# PCB-BI8-3x5C3.net
KiCad netlist of a schematic drawn in EAGLE
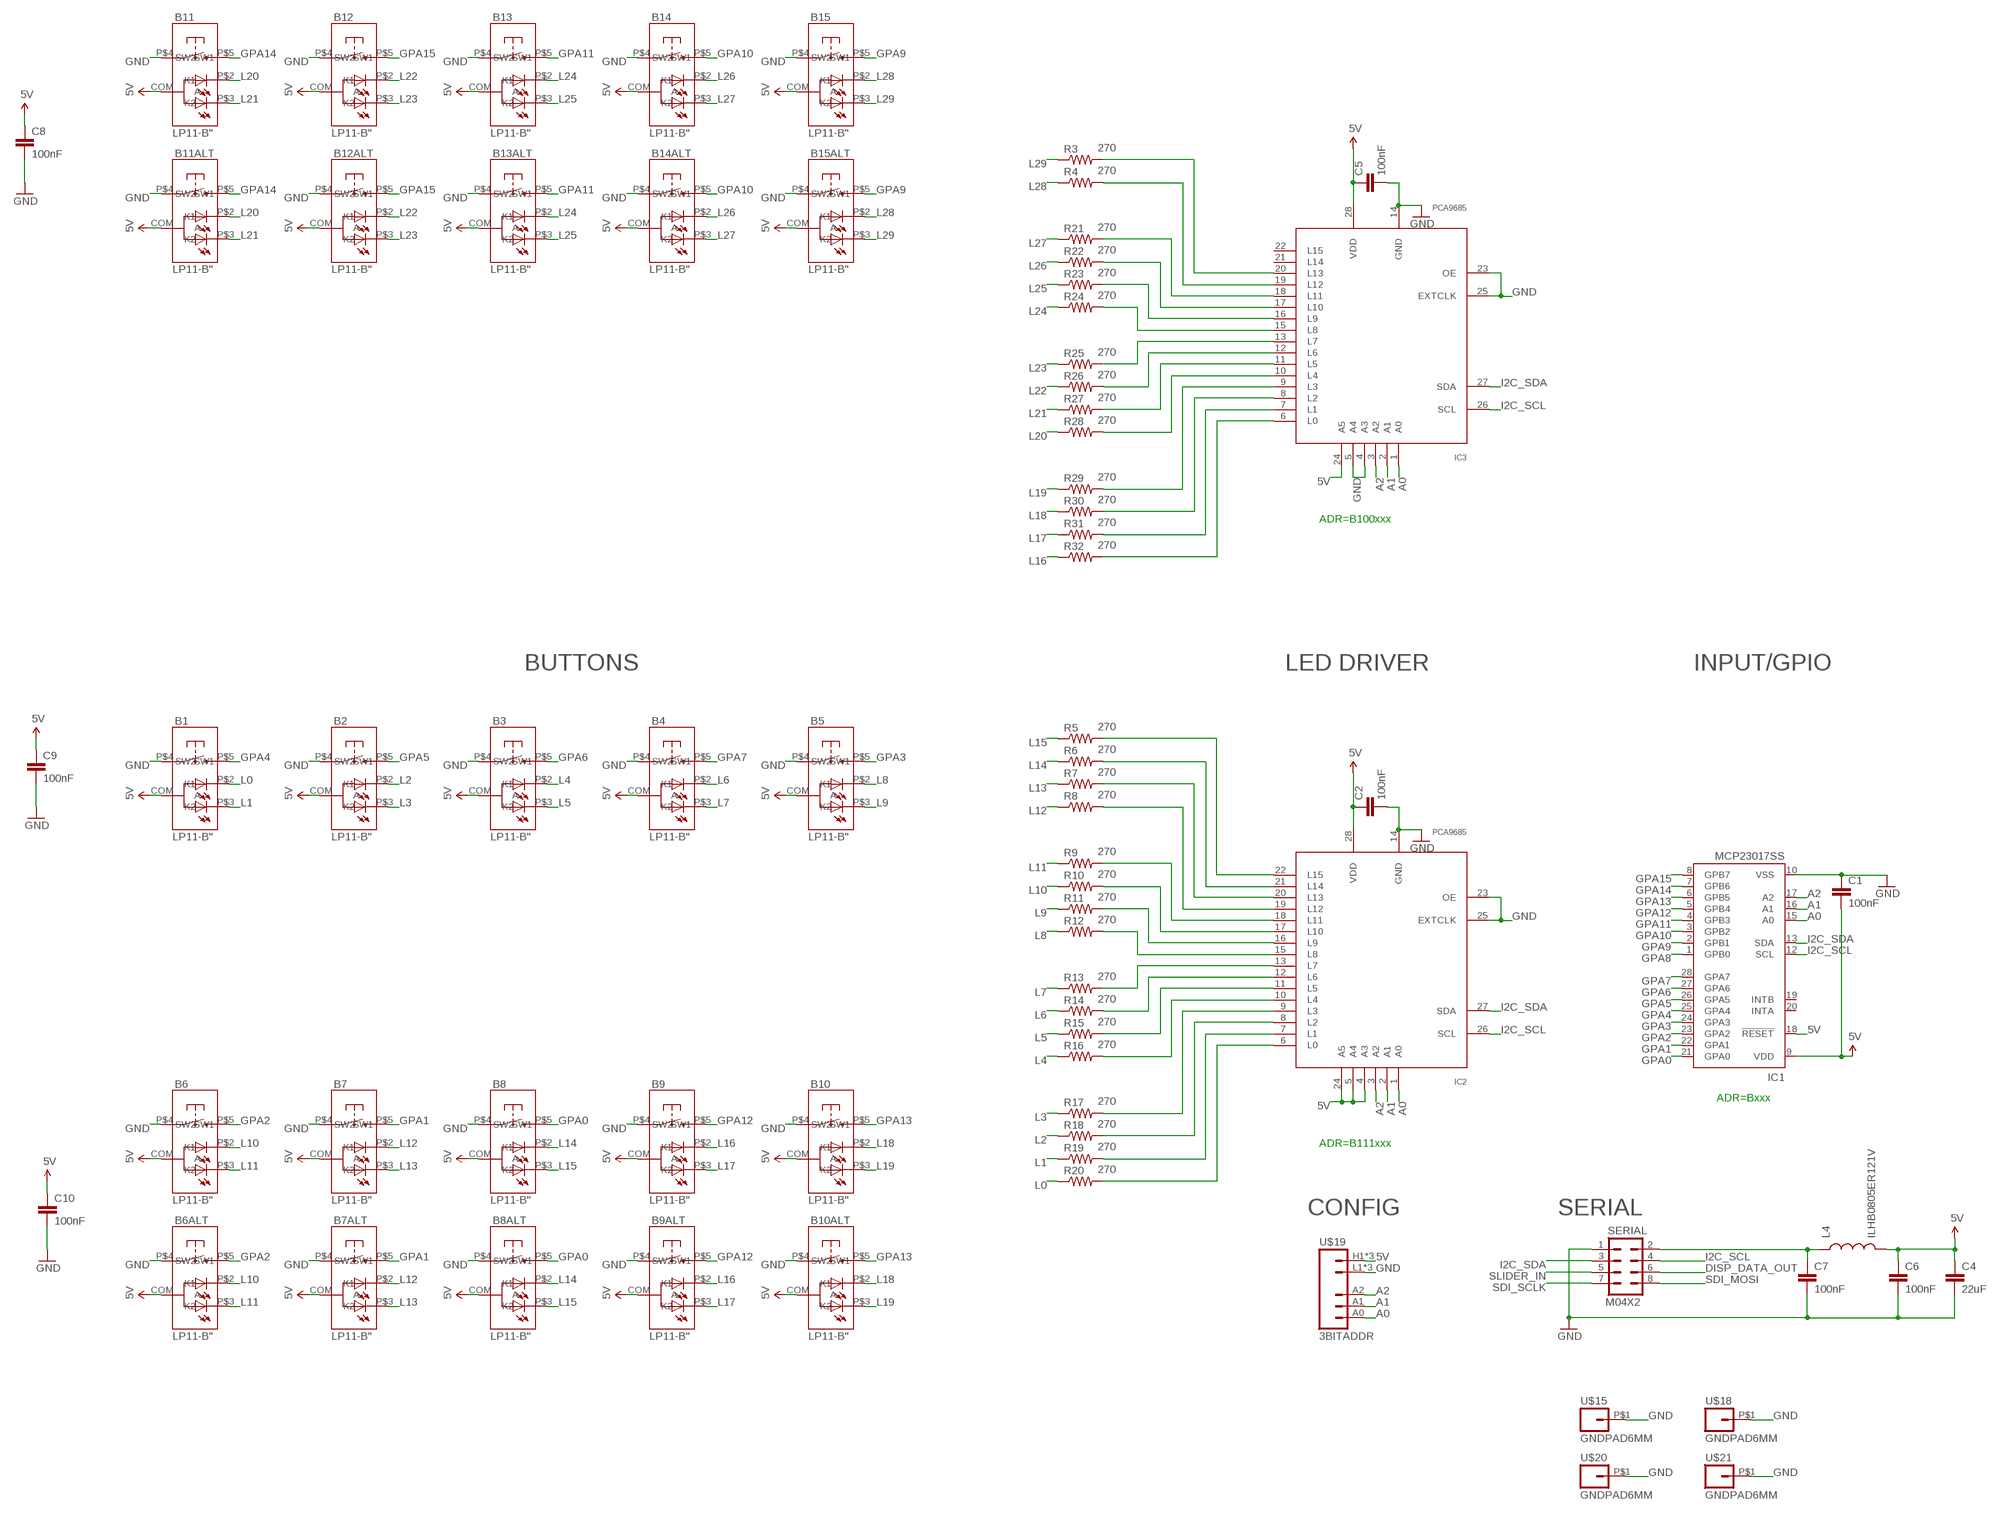
[diagram p0: schematic, sheet 1]

(export (version "E")
  (design (tool "Eeschema 10.0.6"))
  (components
    (comp (ref "B1")
      (value "LP11-B\"")
      (footprint "eagle-import:LP11")
      (libsource (lib "eagle-import") (part "LP11-B{dblquote}"))
    )
    (comp (ref "B2")
      (value "LP11-B\"")
      (footprint "eagle-import:LP11")
      (libsource (lib "eagle-import") (part "LP11-B{dblquote}"))
    )
    (comp (ref "B3")
      (value "LP11-B\"")
      (footprint "eagle-import:LP11")
      (libsource (lib "eagle-import") (part "LP11-B{dblquote}"))
    )
    (comp (ref "B4")
      (value "LP11-B\"")
      (footprint "eagle-import:LP11")
      (libsource (lib "eagle-import") (part "LP11-B{dblquote}"))
    )
    (comp (ref "B5")
      (value "LP11-B\"")
      (footprint "eagle-import:LP11")
      (libsource (lib "eagle-import") (part "LP11-B{dblquote}"))
    )
    (comp (ref "B6")
      (value "LP11-B\"")
      (footprint "eagle-import:LP11")
      (libsource (lib "eagle-import") (part "LP11-B{dblquote}"))
    )
    (comp (ref "B6ALT")
      (value "LP11-B\"")
      (footprint "eagle-import:LP11")
      (libsource (lib "eagle-import") (part "LP11-B{dblquote}"))
    )
    (comp (ref "B7")
      (value "LP11-B\"")
      (footprint "eagle-import:LP11")
      (libsource (lib "eagle-import") (part "LP11-B{dblquote}"))
    )
    (comp (ref "B7ALT")
      (value "LP11-B\"")
      (footprint "eagle-import:LP11")
      (libsource (lib "eagle-import") (part "LP11-B{dblquote}"))
    )
    (comp (ref "B8")
      (value "LP11-B\"")
      (footprint "eagle-import:LP11")
      (libsource (lib "eagle-import") (part "LP11-B{dblquote}"))
    )
    (comp (ref "B8ALT")
      (value "LP11-B\"")
      (footprint "eagle-import:LP11")
      (libsource (lib "eagle-import") (part "LP11-B{dblquote}"))
    )
    (comp (ref "B9")
      (value "LP11-B\"")
      (footprint "eagle-import:LP11")
      (libsource (lib "eagle-import") (part "LP11-B{dblquote}"))
    )
    (comp (ref "B9ALT")
      (value "LP11-B\"")
      (footprint "eagle-import:LP11")
      (libsource (lib "eagle-import") (part "LP11-B{dblquote}"))
    )
    (comp (ref "B10")
      (value "LP11-B\"")
      (footprint "eagle-import:LP11")
      (libsource (lib "eagle-import") (part "LP11-B{dblquote}"))
    )
    (comp (ref "B10ALT")
      (value "LP11-B\"")
      (footprint "eagle-import:LP11")
      (libsource (lib "eagle-import") (part "LP11-B{dblquote}"))
    )
    (comp (ref "B11")
      (value "LP11-B\"")
      (footprint "eagle-import:LP11")
      (libsource (lib "eagle-import") (part "LP11-B{dblquote}"))
    )
    (comp (ref "B11ALT")
      (value "LP11-B\"")
      (footprint "eagle-import:LP11")
      (libsource (lib "eagle-import") (part "LP11-B{dblquote}"))
    )
    (comp (ref "B12")
      (value "LP11-B\"")
      (footprint "eagle-import:LP11")
      (libsource (lib "eagle-import") (part "LP11-B{dblquote}"))
    )
    (comp (ref "B12ALT")
      (value "LP11-B\"")
      (footprint "eagle-import:LP11")
      (libsource (lib "eagle-import") (part "LP11-B{dblquote}"))
    )
    (comp (ref "B13")
      (value "LP11-B\"")
      (footprint "eagle-import:LP11")
      (libsource (lib "eagle-import") (part "LP11-B{dblquote}"))
    )
    (comp (ref "B13ALT")
      (value "LP11-B\"")
      (footprint "eagle-import:LP11")
      (libsource (lib "eagle-import") (part "LP11-B{dblquote}"))
    )
    (comp (ref "B14")
      (value "LP11-B\"")
      (footprint "eagle-import:LP11")
      (libsource (lib "eagle-import") (part "LP11-B{dblquote}"))
    )
    (comp (ref "B14ALT")
      (value "LP11-B\"")
      (footprint "eagle-import:LP11")
      (libsource (lib "eagle-import") (part "LP11-B{dblquote}"))
    )
    (comp (ref "B15")
      (value "LP11-B\"")
      (footprint "eagle-import:LP11")
      (libsource (lib "eagle-import") (part "LP11-B{dblquote}"))
    )
    (comp (ref "B15ALT")
      (value "LP11-B\"")
      (footprint "eagle-import:LP11")
      (libsource (lib "eagle-import") (part "LP11-B{dblquote}"))
    )
    (comp (ref "C1")
      (value "100nF")
      (footprint "eagle-import:0603-CAP")
      (libsource (lib "eagle-import") (part "CAP0603-CAP"))
    )
    (comp (ref "C2")
      (value "100nF")
      (footprint "eagle-import:0603-CAP")
      (libsource (lib "eagle-import") (part "CAP0603-CAP"))
    )
    (comp (ref "C4")
      (value "22uF")
      (footprint "eagle-import:0805")
      (libsource (lib "eagle-import") (part "CAP0805"))
    )
    (comp (ref "C5")
      (value "100nF")
      (footprint "eagle-import:0603-CAP")
      (libsource (lib "eagle-import") (part "CAP0603-CAP"))
    )
    (comp (ref "C6")
      (value "100nF")
      (footprint "eagle-import:0603-CAP")
      (libsource (lib "eagle-import") (part "CAP0603-CAP"))
    )
    (comp (ref "C7")
      (value "100nF")
      (footprint "eagle-import:0603-CAP")
      (libsource (lib "eagle-import") (part "CAP0603-CAP"))
    )
    (comp (ref "C8")
      (value "100nF")
      (footprint "eagle-import:0603-CAP")
      (libsource (lib "eagle-import") (part "CAP0603-CAP"))
    )
    (comp (ref "C9")
      (value "100nF")
      (footprint "eagle-import:0603-CAP")
      (libsource (lib "eagle-import") (part "CAP0603-CAP"))
    )
    (comp (ref "C10")
      (value "100nF")
      (footprint "eagle-import:0603-CAP")
      (libsource (lib "eagle-import") (part "CAP0603-CAP"))
    )
    (comp (ref "IC1")
      (value "MCP23017SS")
      (footprint "eagle-import:SSOP28")
      (fields
        (field (name "MF") "MICROCHIP")
        (field (name "MPN") "MCP23017-E/SS")
        (field (name "MPN_1") "MCP23017-E/SS")
        (field (name "OC_FARNELL") "1467674")
        (field (name "OC_NEWARK") "31K2960")
      )
      (libsource (lib "eagle-import") (part "MCP23017SS"))
    )
    (comp (ref "IC2")
      (value "PCA9685")
      (footprint "eagle-import:TSSOP28")
      (libsource (lib "eagle-import") (part "PCA9685"))
    )
    (comp (ref "IC3")
      (value "PCA9685")
      (footprint "eagle-import:TSSOP28")
      (libsource (lib "eagle-import") (part "PCA9685"))
    )
    (comp (ref "L4")
      (value "ILHB0805ER121V")
      (footprint "eagle-import:0805")
      (libsource (lib "eagle-import") (part "INDUCTOR0805"))
    )
    (comp (ref "R3")
      (value "270")
      (footprint "eagle-import:0603-RES")
      (libsource (lib "eagle-import") (part "RESISTOR0603-RES"))
    )
    (comp (ref "R4")
      (value "270")
      (footprint "eagle-import:0603-RES")
      (libsource (lib "eagle-import") (part "RESISTOR0603-RES"))
    )
    (comp (ref "R5")
      (value "270")
      (footprint "eagle-import:0603-RES")
      (libsource (lib "eagle-import") (part "RESISTOR0603-RES"))
    )
    (comp (ref "R6")
      (value "270")
      (footprint "eagle-import:0603-RES")
      (libsource (lib "eagle-import") (part "RESISTOR0603-RES"))
    )
    (comp (ref "R7")
      (value "270")
      (footprint "eagle-import:0603-RES")
      (libsource (lib "eagle-import") (part "RESISTOR0603-RES"))
    )
    (comp (ref "R8")
      (value "270")
      (footprint "eagle-import:0603-RES")
      (libsource (lib "eagle-import") (part "RESISTOR0603-RES"))
    )
    (comp (ref "R9")
      (value "270")
      (footprint "eagle-import:0603-RES")
      (libsource (lib "eagle-import") (part "RESISTOR0603-RES"))
    )
    (comp (ref "R10")
      (value "270")
      (footprint "eagle-import:0603-RES")
      (libsource (lib "eagle-import") (part "RESISTOR0603-RES"))
    )
    (comp (ref "R11")
      (value "270")
      (footprint "eagle-import:0603-RES")
      (libsource (lib "eagle-import") (part "RESISTOR0603-RES"))
    )
    (comp (ref "R12")
      (value "270")
      (footprint "eagle-import:0603-RES")
      (libsource (lib "eagle-import") (part "RESISTOR0603-RES"))
    )
    (comp (ref "R13")
      (value "270")
      (footprint "eagle-import:0603-RES")
      (libsource (lib "eagle-import") (part "RESISTOR0603-RES"))
    )
    (comp (ref "R14")
      (value "270")
      (footprint "eagle-import:0603-RES")
      (libsource (lib "eagle-import") (part "RESISTOR0603-RES"))
    )
    (comp (ref "R15")
      (value "270")
      (footprint "eagle-import:0603-RES")
      (libsource (lib "eagle-import") (part "RESISTOR0603-RES"))
    )
    (comp (ref "R16")
      (value "270")
      (footprint "eagle-import:0603-RES")
      (libsource (lib "eagle-import") (part "RESISTOR0603-RES"))
    )
    (comp (ref "R17")
      (value "270")
      (footprint "eagle-import:0603-RES")
      (libsource (lib "eagle-import") (part "RESISTOR0603-RES"))
    )
    (comp (ref "R18")
      (value "270")
      (footprint "eagle-import:0603-RES")
      (libsource (lib "eagle-import") (part "RESISTOR0603-RES"))
    )
    (comp (ref "R19")
      (value "270")
      (footprint "eagle-import:0603-RES")
      (libsource (lib "eagle-import") (part "RESISTOR0603-RES"))
    )
    (comp (ref "R20")
      (value "270")
      (footprint "eagle-import:0603-RES")
      (libsource (lib "eagle-import") (part "RESISTOR0603-RES"))
    )
    (comp (ref "R21")
      (value "270")
      (footprint "eagle-import:0603-RES")
      (libsource (lib "eagle-import") (part "RESISTOR0603-RES"))
    )
    (comp (ref "R22")
      (value "270")
      (footprint "eagle-import:0603-RES")
      (libsource (lib "eagle-import") (part "RESISTOR0603-RES"))
    )
    (comp (ref "R23")
      (value "270")
      (footprint "eagle-import:0603-RES")
      (libsource (lib "eagle-import") (part "RESISTOR0603-RES"))
    )
    (comp (ref "R24")
      (value "270")
      (footprint "eagle-import:0603-RES")
      (libsource (lib "eagle-import") (part "RESISTOR0603-RES"))
    )
    (comp (ref "R25")
      (value "270")
      (footprint "eagle-import:0603-RES")
      (libsource (lib "eagle-import") (part "RESISTOR0603-RES"))
    )
    (comp (ref "R26")
      (value "270")
      (footprint "eagle-import:0603-RES")
      (libsource (lib "eagle-import") (part "RESISTOR0603-RES"))
    )
    (comp (ref "R27")
      (value "270")
      (footprint "eagle-import:0603-RES")
      (libsource (lib "eagle-import") (part "RESISTOR0603-RES"))
    )
    (comp (ref "R28")
      (value "270")
      (footprint "eagle-import:0603-RES")
      (libsource (lib "eagle-import") (part "RESISTOR0603-RES"))
    )
    (comp (ref "R29")
      (value "270")
      (footprint "eagle-import:0603-RES")
      (libsource (lib "eagle-import") (part "RESISTOR0603-RES"))
    )
    (comp (ref "R30")
      (value "270")
      (footprint "eagle-import:0603-RES")
      (libsource (lib "eagle-import") (part "RESISTOR0603-RES"))
    )
    (comp (ref "R31")
      (value "270")
      (footprint "eagle-import:0603-RES")
      (libsource (lib "eagle-import") (part "RESISTOR0603-RES"))
    )
    (comp (ref "R32")
      (value "270")
      (footprint "eagle-import:0603-RES")
      (libsource (lib "eagle-import") (part "RESISTOR0603-RES"))
    )
    (comp (ref "SERIAL")
      (value "M04X2")
      (footprint "eagle-import:2X4")
      (libsource (lib "eagle-import") (part "M04X2"))
    )
    (comp (ref "U$15")
      (value "GNDPAD6MM")
      (footprint "eagle-import:3.2MMPAD6MM")
      (libsource (lib "eagle-import") (part "GNDPAD6MM"))
    )
    (comp (ref "U$18")
      (value "GNDPAD6MM")
      (footprint "eagle-import:3.2MMPAD6MM")
      (libsource (lib "eagle-import") (part "GNDPAD6MM"))
    )
    (comp (ref "U$19")
      (value "3BITADDR")
      (footprint "eagle-import:3BITADDR")
      (libsource (lib "eagle-import") (part "3BITADDR"))
    )
    (comp (ref "U$20")
      (value "GNDPAD6MM")
      (footprint "eagle-import:3.2MMPAD6MM")
      (libsource (lib "eagle-import") (part "GNDPAD6MM"))
    )
    (comp (ref "U$21")
      (value "GNDPAD6MM")
      (footprint "eagle-import:3.2MMPAD6MM")
      (libsource (lib "eagle-import") (part "GNDPAD6MM"))
    )
  )
  (nets
    (net (code "1") (name "5V") (class "Default")
      (node (ref "B1") (pin "COM") (pinfunction "A_COM") (pintype "bidirectional"))
      (node (ref "B10") (pin "COM") (pinfunction "A_COM") (pintype "bidirectional"))
      (node (ref "B10ALT") (pin "COM") (pinfunction "A_COM") (pintype "bidirectional"))
      (node (ref "B11") (pin "COM") (pinfunction "A_COM") (pintype "bidirectional"))
      (node (ref "B11ALT") (pin "COM") (pinfunction "A_COM") (pintype "bidirectional"))
      (node (ref "B12") (pin "COM") (pinfunction "A_COM") (pintype "bidirectional"))
      (node (ref "B12ALT") (pin "COM") (pinfunction "A_COM") (pintype "bidirectional"))
      (node (ref "B13") (pin "COM") (pinfunction "A_COM") (pintype "bidirectional"))
      (node (ref "B13ALT") (pin "COM") (pinfunction "A_COM") (pintype "bidirectional"))
      (node (ref "B14") (pin "COM") (pinfunction "A_COM") (pintype "bidirectional"))
      (node (ref "B14ALT") (pin "COM") (pinfunction "A_COM") (pintype "bidirectional"))
      (node (ref "B15") (pin "COM") (pinfunction "A_COM") (pintype "bidirectional"))
      (node (ref "B15ALT") (pin "COM") (pinfunction "A_COM") (pintype "bidirectional"))
      (node (ref "B2") (pin "COM") (pinfunction "A_COM") (pintype "bidirectional"))
      (node (ref "B3") (pin "COM") (pinfunction "A_COM") (pintype "bidirectional"))
      (node (ref "B4") (pin "COM") (pinfunction "A_COM") (pintype "bidirectional"))
      (node (ref "B5") (pin "COM") (pinfunction "A_COM") (pintype "bidirectional"))
      (node (ref "B6") (pin "COM") (pinfunction "A_COM") (pintype "bidirectional"))
      (node (ref "B6ALT") (pin "COM") (pinfunction "A_COM") (pintype "bidirectional"))
      (node (ref "B7") (pin "COM") (pinfunction "A_COM") (pintype "bidirectional"))
      (node (ref "B7ALT") (pin "COM") (pinfunction "A_COM") (pintype "bidirectional"))
      (node (ref "B8") (pin "COM") (pinfunction "A_COM") (pintype "bidirectional"))
      (node (ref "B8ALT") (pin "COM") (pinfunction "A_COM") (pintype "bidirectional"))
      (node (ref "B9") (pin "COM") (pinfunction "A_COM") (pintype "bidirectional"))
      (node (ref "B9ALT") (pin "COM") (pinfunction "A_COM") (pintype "bidirectional"))
      (node (ref "C1") (pin "2") (pinfunction "2_2") (pintype "passive"))
      (node (ref "C10") (pin "1") (pinfunction "1_1") (pintype "passive"))
      (node (ref "C2") (pin "1") (pinfunction "1_1") (pintype "passive"))
      (node (ref "C4") (pin "1") (pinfunction "1_1") (pintype "passive"))
      (node (ref "C5") (pin "1") (pinfunction "1_1") (pintype "passive"))
      (node (ref "C6") (pin "1") (pinfunction "1_1") (pintype "passive"))
      (node (ref "C8") (pin "1") (pinfunction "1_1") (pintype "passive"))
      (node (ref "C9") (pin "1") (pinfunction "1_1") (pintype "passive"))
      (node (ref "IC1") (pin "18") (pinfunction "~{RESET}_18") (pintype "input"))
      (node (ref "IC1") (pin "9") (pinfunction "VDD_9") (pintype "power_in"))
      (node (ref "IC2") (pin "24") (pinfunction "A5_24") (pintype "input"))
      (node (ref "IC2") (pin "28") (pinfunction "VDD_28") (pintype "power_in"))
      (node (ref "IC2") (pin "4") (pinfunction "A3_4") (pintype "input"))
      (node (ref "IC2") (pin "5") (pinfunction "A4_5") (pintype "input"))
      (node (ref "IC3") (pin "24") (pinfunction "A5_24") (pintype "input"))
      (node (ref "IC3") (pin "28") (pinfunction "VDD_28") (pintype "power_in"))
      (node (ref "L4") (pin "2") (pinfunction "2_2") (pintype "passive"))
      (node (ref "U$19") (pin "H1") (pinfunction "VCC_H1") (pintype "passive"))
      (node (ref "U$19") (pin "H2") (pinfunction "VCC_H2") (pintype "passive"))
      (node (ref "U$19") (pin "H3") (pinfunction "VCC_H3") (pintype "passive"))
    )
    (net (code "2") (name "A0") (class "Default")
      (node (ref "IC1") (pin "15") (pinfunction "A0_15") (pintype "input"))
      (node (ref "IC2") (pin "1") (pinfunction "A0_1") (pintype "input"))
      (node (ref "IC3") (pin "1") (pinfunction "A0_1") (pintype "input"))
      (node (ref "U$19") (pin "A0") (pinfunction "A0_A0") (pintype "passive"))
    )
    (net (code "3") (name "A1") (class "Default")
      (node (ref "IC1") (pin "16") (pinfunction "A1_16") (pintype "input"))
      (node (ref "IC2") (pin "2") (pinfunction "A1_2") (pintype "input"))
      (node (ref "IC3") (pin "2") (pinfunction "A1_2") (pintype "input"))
      (node (ref "U$19") (pin "A1") (pinfunction "A1_A1") (pintype "passive"))
    )
    (net (code "4") (name "A2") (class "Default")
      (node (ref "IC1") (pin "17") (pinfunction "A2_17") (pintype "input"))
      (node (ref "IC2") (pin "3") (pinfunction "A2_3") (pintype "input"))
      (node (ref "IC3") (pin "3") (pinfunction "A2_3") (pintype "input"))
      (node (ref "U$19") (pin "A2") (pinfunction "A2_A2") (pintype "passive"))
    )
    (net (code "5") (name "DISP_DATA_OUT") (class "Default")
      (node (ref "SERIAL") (pin "6") (pinfunction "6_6") (pintype "passive"))
    )
    (net (code "6") (name "GND") (class "Default")
      (node (ref "B1") (pin "P$4") (pinfunction "SW1_P$4") (pintype "bidirectional"))
      (node (ref "B10") (pin "P$4") (pinfunction "SW1_P$4") (pintype "bidirectional"))
      (node (ref "B10ALT") (pin "P$4") (pinfunction "SW1_P$4") (pintype "bidirectional"))
      (node (ref "B11") (pin "P$4") (pinfunction "SW1_P$4") (pintype "bidirectional"))
      (node (ref "B11ALT") (pin "P$4") (pinfunction "SW1_P$4") (pintype "bidirectional"))
      (node (ref "B12") (pin "P$4") (pinfunction "SW1_P$4") (pintype "bidirectional"))
      (node (ref "B12ALT") (pin "P$4") (pinfunction "SW1_P$4") (pintype "bidirectional"))
      (node (ref "B13") (pin "P$4") (pinfunction "SW1_P$4") (pintype "bidirectional"))
      (node (ref "B13ALT") (pin "P$4") (pinfunction "SW1_P$4") (pintype "bidirectional"))
      (node (ref "B14") (pin "P$4") (pinfunction "SW1_P$4") (pintype "bidirectional"))
      (node (ref "B14ALT") (pin "P$4") (pinfunction "SW1_P$4") (pintype "bidirectional"))
      (node (ref "B15") (pin "P$4") (pinfunction "SW1_P$4") (pintype "bidirectional"))
      (node (ref "B15ALT") (pin "P$4") (pinfunction "SW1_P$4") (pintype "bidirectional"))
      (node (ref "B2") (pin "P$4") (pinfunction "SW1_P$4") (pintype "bidirectional"))
      (node (ref "B3") (pin "P$4") (pinfunction "SW1_P$4") (pintype "bidirectional"))
      (node (ref "B4") (pin "P$4") (pinfunction "SW1_P$4") (pintype "bidirectional"))
      (node (ref "B5") (pin "P$4") (pinfunction "SW1_P$4") (pintype "bidirectional"))
      (node (ref "B6") (pin "P$4") (pinfunction "SW1_P$4") (pintype "bidirectional"))
      (node (ref "B6ALT") (pin "P$4") (pinfunction "SW1_P$4") (pintype "bidirectional"))
      (node (ref "B7") (pin "P$4") (pinfunction "SW1_P$4") (pintype "bidirectional"))
      (node (ref "B7ALT") (pin "P$4") (pinfunction "SW1_P$4") (pintype "bidirectional"))
      (node (ref "B8") (pin "P$4") (pinfunction "SW1_P$4") (pintype "bidirectional"))
      (node (ref "B8ALT") (pin "P$4") (pinfunction "SW1_P$4") (pintype "bidirectional"))
      (node (ref "B9") (pin "P$4") (pinfunction "SW1_P$4") (pintype "bidirectional"))
      (node (ref "B9ALT") (pin "P$4") (pinfunction "SW1_P$4") (pintype "bidirectional"))
      (node (ref "C1") (pin "1") (pinfunction "1_1") (pintype "passive"))
      (node (ref "C10") (pin "2") (pinfunction "2_2") (pintype "passive"))
      (node (ref "C2") (pin "2") (pinfunction "2_2") (pintype "passive"))
      (node (ref "C4") (pin "2") (pinfunction "2_2") (pintype "passive"))
      (node (ref "C5") (pin "2") (pinfunction "2_2") (pintype "passive"))
      (node (ref "C6") (pin "2") (pinfunction "2_2") (pintype "passive"))
      (node (ref "C7") (pin "2") (pinfunction "2_2") (pintype "passive"))
      (node (ref "C8") (pin "2") (pinfunction "2_2") (pintype "passive"))
      (node (ref "C9") (pin "2") (pinfunction "2_2") (pintype "passive"))
      (node (ref "IC1") (pin "10") (pinfunction "VSS_10") (pintype "power_in"))
      (node (ref "IC2") (pin "14") (pinfunction "GND_14") (pintype "power_in"))
      (node (ref "IC2") (pin "23") (pinfunction "OE_23") (pintype "input"))
      (node (ref "IC2") (pin "25") (pinfunction "EXTCLK_25") (pintype "input"))
      (node (ref "IC3") (pin "14") (pinfunction "GND_14") (pintype "power_in"))
      (node (ref "IC3") (pin "23") (pinfunction "OE_23") (pintype "input"))
      (node (ref "IC3") (pin "25") (pinfunction "EXTCLK_25") (pintype "input"))
      (node (ref "IC3") (pin "4") (pinfunction "A3_4") (pintype "input"))
      (node (ref "IC3") (pin "5") (pinfunction "A4_5") (pintype "input"))
      (node (ref "SERIAL") (pin "1") (pinfunction "1_1") (pintype "passive"))
      (node (ref "U$15") (pin "P$1") (pinfunction "1_P$1") (pintype "passive"))
      (node (ref "U$18") (pin "P$1") (pinfunction "1_P$1") (pintype "passive"))
      (node (ref "U$19") (pin "L1") (pinfunction "GND_L1") (pintype "passive"))
      (node (ref "U$19") (pin "L2") (pinfunction "GND_L2") (pintype "passive"))
      (node (ref "U$19") (pin "L3") (pinfunction "GND_L3") (pintype "passive"))
      (node (ref "U$20") (pin "P$1") (pinfunction "1_P$1") (pintype "passive"))
      (node (ref "U$21") (pin "P$1") (pinfunction "1_P$1") (pintype "passive"))
    )
    (net (code "7") (name "GPA0") (class "Default")
      (node (ref "B8") (pin "P$5") (pinfunction "SW2_P$5") (pintype "bidirectional"))
      (node (ref "B8ALT") (pin "P$5") (pinfunction "SW2_P$5") (pintype "bidirectional"))
      (node (ref "IC1") (pin "21") (pinfunction "GPA0_21") (pintype "bidirectional"))
    )
    (net (code "8") (name "GPA1") (class "Default")
      (node (ref "B7") (pin "P$5") (pinfunction "SW2_P$5") (pintype "bidirectional"))
      (node (ref "B7ALT") (pin "P$5") (pinfunction "SW2_P$5") (pintype "bidirectional"))
      (node (ref "IC1") (pin "22") (pinfunction "GPA1_22") (pintype "bidirectional"))
    )
    (net (code "9") (name "GPA2") (class "Default")
      (node (ref "B6") (pin "P$5") (pinfunction "SW2_P$5") (pintype "bidirectional"))
      (node (ref "B6ALT") (pin "P$5") (pinfunction "SW2_P$5") (pintype "bidirectional"))
      (node (ref "IC1") (pin "23") (pinfunction "GPA2_23") (pintype "bidirectional"))
    )
    (net (code "10") (name "GPA3") (class "Default")
      (node (ref "B5") (pin "P$5") (pinfunction "SW2_P$5") (pintype "bidirectional"))
      (node (ref "IC1") (pin "24") (pinfunction "GPA3_24") (pintype "bidirectional"))
    )
    (net (code "11") (name "GPA4") (class "Default")
      (node (ref "B1") (pin "P$5") (pinfunction "SW2_P$5") (pintype "bidirectional"))
      (node (ref "IC1") (pin "25") (pinfunction "GPA4_25") (pintype "bidirectional"))
    )
    (net (code "12") (name "GPA5") (class "Default")
      (node (ref "B2") (pin "P$5") (pinfunction "SW2_P$5") (pintype "bidirectional"))
      (node (ref "IC1") (pin "26") (pinfunction "GPA5_26") (pintype "bidirectional"))
    )
    (net (code "13") (name "GPA6") (class "Default")
      (node (ref "B3") (pin "P$5") (pinfunction "SW2_P$5") (pintype "bidirectional"))
      (node (ref "IC1") (pin "27") (pinfunction "GPA6_27") (pintype "bidirectional"))
    )
    (net (code "14") (name "GPA7") (class "Default")
      (node (ref "B4") (pin "P$5") (pinfunction "SW2_P$5") (pintype "bidirectional"))
      (node (ref "IC1") (pin "28") (pinfunction "GPA7_28") (pintype "bidirectional"))
    )
    (net (code "15") (name "GPA8") (class "Default")
      (node (ref "IC1") (pin "1") (pinfunction "GPB0_1") (pintype "bidirectional"))
    )
    (net (code "16") (name "GPA9") (class "Default")
      (node (ref "B15") (pin "P$5") (pinfunction "SW2_P$5") (pintype "bidirectional"))
      (node (ref "B15ALT") (pin "P$5") (pinfunction "SW2_P$5") (pintype "bidirectional"))
      (node (ref "IC1") (pin "2") (pinfunction "GPB1_2") (pintype "bidirectional"))
    )
    (net (code "17") (name "GPA10") (class "Default")
      (node (ref "B14") (pin "P$5") (pinfunction "SW2_P$5") (pintype "bidirectional"))
      (node (ref "B14ALT") (pin "P$5") (pinfunction "SW2_P$5") (pintype "bidirectional"))
      (node (ref "IC1") (pin "3") (pinfunction "GPB2_3") (pintype "bidirectional"))
    )
    (net (code "18") (name "GPA11") (class "Default")
      (node (ref "B13") (pin "P$5") (pinfunction "SW2_P$5") (pintype "bidirectional"))
      (node (ref "B13ALT") (pin "P$5") (pinfunction "SW2_P$5") (pintype "bidirectional"))
      (node (ref "IC1") (pin "4") (pinfunction "GPB3_4") (pintype "bidirectional"))
    )
    (net (code "19") (name "GPA12") (class "Default")
      (node (ref "B9") (pin "P$5") (pinfunction "SW2_P$5") (pintype "bidirectional"))
      (node (ref "B9ALT") (pin "P$5") (pinfunction "SW2_P$5") (pintype "bidirectional"))
      (node (ref "IC1") (pin "5") (pinfunction "GPB4_5") (pintype "bidirectional"))
    )
    (net (code "20") (name "GPA13") (class "Default")
      (node (ref "B10") (pin "P$5") (pinfunction "SW2_P$5") (pintype "bidirectional"))
      (node (ref "B10ALT") (pin "P$5") (pinfunction "SW2_P$5") (pintype "bidirectional"))
      (node (ref "IC1") (pin "6") (pinfunction "GPB5_6") (pintype "bidirectional"))
    )
    (net (code "21") (name "GPA14") (class "Default")
      (node (ref "B11") (pin "P$5") (pinfunction "SW2_P$5") (pintype "bidirectional"))
      (node (ref "B11ALT") (pin "P$5") (pinfunction "SW2_P$5") (pintype "bidirectional"))
      (node (ref "IC1") (pin "7") (pinfunction "GPB6_7") (pintype "bidirectional"))
    )
    (net (code "22") (name "GPA15") (class "Default")
      (node (ref "B12") (pin "P$5") (pinfunction "SW2_P$5") (pintype "bidirectional"))
      (node (ref "B12ALT") (pin "P$5") (pinfunction "SW2_P$5") (pintype "bidirectional"))
      (node (ref "IC1") (pin "8") (pinfunction "GPB7_8") (pintype "bidirectional"))
    )
    (net (code "23") (name "I2C_SCL") (class "Default")
      (node (ref "IC1") (pin "12") (pinfunction "SCL_12") (pintype "input"))
      (node (ref "IC2") (pin "26") (pinfunction "SCL_26") (pintype "input"))
      (node (ref "IC3") (pin "26") (pinfunction "SCL_26") (pintype "input"))
      (node (ref "SERIAL") (pin "4") (pinfunction "4_4") (pintype "passive"))
    )
    (net (code "24") (name "I2C_SDA") (class "Default")
      (node (ref "IC1") (pin "13") (pinfunction "SDA_13") (pintype "bidirectional"))
      (node (ref "IC2") (pin "27") (pinfunction "SDA_27") (pintype "input"))
      (node (ref "IC3") (pin "27") (pinfunction "SDA_27") (pintype "input"))
      (node (ref "SERIAL") (pin "3") (pinfunction "3_3") (pintype "passive"))
    )
    (net (code "25") (name "L0") (class "Default")
      (node (ref "B1") (pin "P$2") (pinfunction "K1_P$2") (pintype "bidirectional"))
      (node (ref "R20") (pin "1") (pinfunction "1_1") (pintype "passive"))
    )
    (net (code "26") (name "L1") (class "Default")
      (node (ref "B1") (pin "P$3") (pinfunction "K2_P$3") (pintype "bidirectional"))
      (node (ref "R19") (pin "1") (pinfunction "1_1") (pintype "passive"))
    )
    (net (code "27") (name "L2") (class "Default")
      (node (ref "B2") (pin "P$2") (pinfunction "K1_P$2") (pintype "bidirectional"))
      (node (ref "R18") (pin "1") (pinfunction "1_1") (pintype "passive"))
    )
    (net (code "28") (name "L3") (class "Default")
      (node (ref "B2") (pin "P$3") (pinfunction "K2_P$3") (pintype "bidirectional"))
      (node (ref "R17") (pin "1") (pinfunction "1_1") (pintype "passive"))
    )
    (net (code "29") (name "L4") (class "Default")
      (node (ref "B3") (pin "P$2") (pinfunction "K1_P$2") (pintype "bidirectional"))
      (node (ref "R16") (pin "1") (pinfunction "1_1") (pintype "passive"))
    )
    (net (code "30") (name "L5") (class "Default")
      (node (ref "B3") (pin "P$3") (pinfunction "K2_P$3") (pintype "bidirectional"))
      (node (ref "R15") (pin "1") (pinfunction "1_1") (pintype "passive"))
    )
    (net (code "31") (name "L6") (class "Default")
      (node (ref "B4") (pin "P$2") (pinfunction "K1_P$2") (pintype "bidirectional"))
      (node (ref "R14") (pin "1") (pinfunction "1_1") (pintype "passive"))
    )
    (net (code "32") (name "L7") (class "Default")
      (node (ref "B4") (pin "P$3") (pinfunction "K2_P$3") (pintype "bidirectional"))
      (node (ref "R13") (pin "1") (pinfunction "1_1") (pintype "passive"))
    )
    (net (code "33") (name "L8") (class "Default")
      (node (ref "B5") (pin "P$2") (pinfunction "K1_P$2") (pintype "bidirectional"))
      (node (ref "R12") (pin "1") (pinfunction "1_1") (pintype "passive"))
    )
    (net (code "34") (name "L9") (class "Default")
      (node (ref "B5") (pin "P$3") (pinfunction "K2_P$3") (pintype "bidirectional"))
      (node (ref "R11") (pin "1") (pinfunction "1_1") (pintype "passive"))
    )
    (net (code "35") (name "L10") (class "Default")
      (node (ref "B6") (pin "P$2") (pinfunction "K1_P$2") (pintype "bidirectional"))
      (node (ref "B6ALT") (pin "P$2") (pinfunction "K1_P$2") (pintype "bidirectional"))
      (node (ref "R10") (pin "1") (pinfunction "1_1") (pintype "passive"))
    )
    (net (code "36") (name "L11") (class "Default")
      (node (ref "B6") (pin "P$3") (pinfunction "K2_P$3") (pintype "bidirectional"))
      (node (ref "B6ALT") (pin "P$3") (pinfunction "K2_P$3") (pintype "bidirectional"))
      (node (ref "R9") (pin "1") (pinfunction "1_1") (pintype "passive"))
    )
    (net (code "37") (name "L12") (class "Default")
      (node (ref "B7") (pin "P$2") (pinfunction "K1_P$2") (pintype "bidirectional"))
      (node (ref "B7ALT") (pin "P$2") (pinfunction "K1_P$2") (pintype "bidirectional"))
      (node (ref "R8") (pin "1") (pinfunction "1_1") (pintype "passive"))
    )
    (net (code "38") (name "L13") (class "Default")
      (node (ref "B7") (pin "P$3") (pinfunction "K2_P$3") (pintype "bidirectional"))
      (node (ref "B7ALT") (pin "P$3") (pinfunction "K2_P$3") (pintype "bidirectional"))
      (node (ref "R7") (pin "1") (pinfunction "1_1") (pintype "passive"))
    )
    (net (code "39") (name "L14") (class "Default")
      (node (ref "B8") (pin "P$2") (pinfunction "K1_P$2") (pintype "bidirectional"))
      (node (ref "B8ALT") (pin "P$2") (pinfunction "K1_P$2") (pintype "bidirectional"))
      (node (ref "R6") (pin "1") (pinfunction "1_1") (pintype "passive"))
    )
    (net (code "40") (name "L15") (class "Default")
      (node (ref "B8") (pin "P$3") (pinfunction "K2_P$3") (pintype "bidirectional"))
      (node (ref "B8ALT") (pin "P$3") (pinfunction "K2_P$3") (pintype "bidirectional"))
      (node (ref "R5") (pin "1") (pinfunction "1_1") (pintype "passive"))
    )
    (net (code "41") (name "L16") (class "Default")
      (node (ref "B9") (pin "P$2") (pinfunction "K1_P$2") (pintype "bidirectional"))
      (node (ref "B9ALT") (pin "P$2") (pinfunction "K1_P$2") (pintype "bidirectional"))
      (node (ref "R32") (pin "1") (pinfunction "1_1") (pintype "passive"))
    )
    (net (code "42") (name "L17") (class "Default")
      (node (ref "B9") (pin "P$3") (pinfunction "K2_P$3") (pintype "bidirectional"))
      (node (ref "B9ALT") (pin "P$3") (pinfunction "K2_P$3") (pintype "bidirectional"))
      (node (ref "R31") (pin "1") (pinfunction "1_1") (pintype "passive"))
    )
    (net (code "43") (name "L18") (class "Default")
      (node (ref "B10") (pin "P$2") (pinfunction "K1_P$2") (pintype "bidirectional"))
      (node (ref "B10ALT") (pin "P$2") (pinfunction "K1_P$2") (pintype "bidirectional"))
      (node (ref "R30") (pin "1") (pinfunction "1_1") (pintype "passive"))
    )
    (net (code "44") (name "L19") (class "Default")
      (node (ref "B10") (pin "P$3") (pinfunction "K2_P$3") (pintype "bidirectional"))
      (node (ref "B10ALT") (pin "P$3") (pinfunction "K2_P$3") (pintype "bidirectional"))
      (node (ref "R29") (pin "1") (pinfunction "1_1") (pintype "passive"))
    )
    (net (code "45") (name "L20") (class "Default")
      (node (ref "B11") (pin "P$2") (pinfunction "K1_P$2") (pintype "bidirectional"))
      (node (ref "B11ALT") (pin "P$2") (pinfunction "K1_P$2") (pintype "bidirectional"))
      (node (ref "R28") (pin "1") (pinfunction "1_1") (pintype "passive"))
    )
    (net (code "46") (name "L21") (class "Default")
      (node (ref "B11") (pin "P$3") (pinfunction "K2_P$3") (pintype "bidirectional"))
      (node (ref "B11ALT") (pin "P$3") (pinfunction "K2_P$3") (pintype "bidirectional"))
      (node (ref "R27") (pin "1") (pinfunction "1_1") (pintype "passive"))
    )
    (net (code "47") (name "L22") (class "Default")
      (node (ref "B12") (pin "P$2") (pinfunction "K1_P$2") (pintype "bidirectional"))
      (node (ref "B12ALT") (pin "P$2") (pinfunction "K1_P$2") (pintype "bidirectional"))
      (node (ref "R26") (pin "1") (pinfunction "1_1") (pintype "passive"))
    )
    (net (code "48") (name "L23") (class "Default")
      (node (ref "B12") (pin "P$3") (pinfunction "K2_P$3") (pintype "bidirectional"))
      (node (ref "B12ALT") (pin "P$3") (pinfunction "K2_P$3") (pintype "bidirectional"))
      (node (ref "R25") (pin "1") (pinfunction "1_1") (pintype "passive"))
    )
    (net (code "49") (name "L24") (class "Default")
      (node (ref "B13") (pin "P$2") (pinfunction "K1_P$2") (pintype "bidirectional"))
      (node (ref "B13ALT") (pin "P$2") (pinfunction "K1_P$2") (pintype "bidirectional"))
      (node (ref "R24") (pin "1") (pinfunction "1_1") (pintype "passive"))
    )
    (net (code "50") (name "L25") (class "Default")
      (node (ref "B13") (pin "P$3") (pinfunction "K2_P$3") (pintype "bidirectional"))
      (node (ref "B13ALT") (pin "P$3") (pinfunction "K2_P$3") (pintype "bidirectional"))
      (node (ref "R23") (pin "1") (pinfunction "1_1") (pintype "passive"))
    )
    (net (code "51") (name "L26") (class "Default")
      (node (ref "B14") (pin "P$2") (pinfunction "K1_P$2") (pintype "bidirectional"))
      (node (ref "B14ALT") (pin "P$2") (pinfunction "K1_P$2") (pintype "bidirectional"))
      (node (ref "R22") (pin "1") (pinfunction "1_1") (pintype "passive"))
    )
    (net (code "52") (name "L27") (class "Default")
      (node (ref "B14") (pin "P$3") (pinfunction "K2_P$3") (pintype "bidirectional"))
      (node (ref "B14ALT") (pin "P$3") (pinfunction "K2_P$3") (pintype "bidirectional"))
      (node (ref "R21") (pin "1") (pinfunction "1_1") (pintype "passive"))
    )
    (net (code "53") (name "L28") (class "Default")
      (node (ref "B15") (pin "P$2") (pinfunction "K1_P$2") (pintype "bidirectional"))
      (node (ref "B15ALT") (pin "P$2") (pinfunction "K1_P$2") (pintype "bidirectional"))
      (node (ref "R4") (pin "1") (pinfunction "1_1") (pintype "passive"))
    )
    (net (code "54") (name "L29") (class "Default")
      (node (ref "B15") (pin "P$3") (pinfunction "K2_P$3") (pintype "bidirectional"))
      (node (ref "B15ALT") (pin "P$3") (pinfunction "K2_P$3") (pintype "bidirectional"))
      (node (ref "R3") (pin "1") (pinfunction "1_1") (pintype "passive"))
    )
    (net (code "55") (name "Net-(C7-Pad1)") (class "Default")
      (node (ref "C7") (pin "1") (pinfunction "1_1") (pintype "passive"))
      (node (ref "L4") (pin "1") (pinfunction "1_1") (pintype "passive"))
      (node (ref "SERIAL") (pin "2") (pinfunction "2_2") (pintype "passive"))
    )
    (net (code "56") (name "Net-(IC2-L0)") (class "Default")
      (node (ref "IC2") (pin "6") (pinfunction "L0_6") (pintype "output"))
      (node (ref "R20") (pin "2") (pinfunction "2_2") (pintype "passive"))
    )
    (net (code "57") (name "Net-(IC2-L1)") (class "Default")
      (node (ref "IC2") (pin "7") (pinfunction "L1_7") (pintype "output"))
      (node (ref "R19") (pin "2") (pinfunction "2_2") (pintype "passive"))
    )
    (net (code "58") (name "Net-(IC2-L2)") (class "Default")
      (node (ref "IC2") (pin "8") (pinfunction "L2_8") (pintype "output"))
      (node (ref "R18") (pin "2") (pinfunction "2_2") (pintype "passive"))
    )
    (net (code "59") (name "Net-(IC2-L3)") (class "Default")
      (node (ref "IC2") (pin "9") (pinfunction "L3_9") (pintype "output"))
      (node (ref "R17") (pin "2") (pinfunction "2_2") (pintype "passive"))
    )
    (net (code "60") (name "Net-(IC2-L4)") (class "Default")
      (node (ref "IC2") (pin "10") (pinfunction "L4_10") (pintype "output"))
      (node (ref "R16") (pin "2") (pinfunction "2_2") (pintype "passive"))
    )
    (net (code "61") (name "Net-(IC2-L5)") (class "Default")
      (node (ref "IC2") (pin "11") (pinfunction "L5_11") (pintype "output"))
      (node (ref "R15") (pin "2") (pinfunction "2_2") (pintype "passive"))
    )
    (net (code "62") (name "Net-(IC2-L6)") (class "Default")
      (node (ref "IC2") (pin "12") (pinfunction "L6_12") (pintype "output"))
      (node (ref "R14") (pin "2") (pinfunction "2_2") (pintype "passive"))
    )
    (net (code "63") (name "Net-(IC2-L7)") (class "Default")
      (node (ref "IC2") (pin "13") (pinfunction "L7_13") (pintype "output"))
      (node (ref "R13") (pin "2") (pinfunction "2_2") (pintype "passive"))
    )
    (net (code "64") (name "Net-(IC2-L8)") (class "Default")
      (node (ref "IC2") (pin "15") (pinfunction "L8_15") (pintype "output"))
      (node (ref "R12") (pin "2") (pinfunction "2_2") (pintype "passive"))
    )
    (net (code "65") (name "Net-(IC2-L9)") (class "Default")
      (node (ref "IC2") (pin "16") (pinfunction "L9_16") (pintype "output"))
      (node (ref "R11") (pin "2") (pinfunction "2_2") (pintype "passive"))
    )
    (net (code "66") (name "Net-(IC2-L10)") (class "Default")
      (node (ref "IC2") (pin "17") (pinfunction "L10_17") (pintype "output"))
      (node (ref "R10") (pin "2") (pinfunction "2_2") (pintype "passive"))
    )
    (net (code "67") (name "Net-(IC2-L11)") (class "Default")
      (node (ref "IC2") (pin "18") (pinfunction "L11_18") (pintype "output"))
      (node (ref "R9") (pin "2") (pinfunction "2_2") (pintype "passive"))
    )
    (net (code "68") (name "Net-(IC2-L12)") (class "Default")
      (node (ref "IC2") (pin "19") (pinfunction "L12_19") (pintype "output"))
      (node (ref "R8") (pin "2") (pinfunction "2_2") (pintype "passive"))
    )
    (net (code "69") (name "Net-(IC2-L13)") (class "Default")
      (node (ref "IC2") (pin "20") (pinfunction "L13_20") (pintype "output"))
      (node (ref "R7") (pin "2") (pinfunction "2_2") (pintype "passive"))
    )
    (net (code "70") (name "Net-(IC2-L14)") (class "Default")
      (node (ref "IC2") (pin "21") (pinfunction "L14_21") (pintype "output"))
      (node (ref "R6") (pin "2") (pinfunction "2_2") (pintype "passive"))
    )
    (net (code "71") (name "Net-(IC2-L15)") (class "Default")
      (node (ref "IC2") (pin "22") (pinfunction "L15_22") (pintype "output"))
      (node (ref "R5") (pin "2") (pinfunction "2_2") (pintype "passive"))
    )
    (net (code "72") (name "Net-(IC3-L0)") (class "Default")
      (node (ref "IC3") (pin "6") (pinfunction "L0_6") (pintype "output"))
      (node (ref "R32") (pin "2") (pinfunction "2_2") (pintype "passive"))
    )
    (net (code "73") (name "Net-(IC3-L1)") (class "Default")
      (node (ref "IC3") (pin "7") (pinfunction "L1_7") (pintype "output"))
      (node (ref "R31") (pin "2") (pinfunction "2_2") (pintype "passive"))
    )
    (net (code "74") (name "Net-(IC3-L2)") (class "Default")
      (node (ref "IC3") (pin "8") (pinfunction "L2_8") (pintype "output"))
      (node (ref "R30") (pin "2") (pinfunction "2_2") (pintype "passive"))
    )
    (net (code "75") (name "Net-(IC3-L3)") (class "Default")
      (node (ref "IC3") (pin "9") (pinfunction "L3_9") (pintype "output"))
      (node (ref "R29") (pin "2") (pinfunction "2_2") (pintype "passive"))
    )
    (net (code "76") (name "Net-(IC3-L4)") (class "Default")
      (node (ref "IC3") (pin "10") (pinfunction "L4_10") (pintype "output"))
      (node (ref "R28") (pin "2") (pinfunction "2_2") (pintype "passive"))
    )
    (net (code "77") (name "Net-(IC3-L5)") (class "Default")
      (node (ref "IC3") (pin "11") (pinfunction "L5_11") (pintype "output"))
      (node (ref "R27") (pin "2") (pinfunction "2_2") (pintype "passive"))
    )
    (net (code "78") (name "Net-(IC3-L6)") (class "Default")
      (node (ref "IC3") (pin "12") (pinfunction "L6_12") (pintype "output"))
      (node (ref "R26") (pin "2") (pinfunction "2_2") (pintype "passive"))
    )
    (net (code "79") (name "Net-(IC3-L7)") (class "Default")
      (node (ref "IC3") (pin "13") (pinfunction "L7_13") (pintype "output"))
      (node (ref "R25") (pin "2") (pinfunction "2_2") (pintype "passive"))
    )
    (net (code "80") (name "Net-(IC3-L8)") (class "Default")
      (node (ref "IC3") (pin "15") (pinfunction "L8_15") (pintype "output"))
      (node (ref "R24") (pin "2") (pinfunction "2_2") (pintype "passive"))
    )
    (net (code "81") (name "Net-(IC3-L9)") (class "Default")
      (node (ref "IC3") (pin "16") (pinfunction "L9_16") (pintype "output"))
      (node (ref "R23") (pin "2") (pinfunction "2_2") (pintype "passive"))
    )
    (net (code "82") (name "Net-(IC3-L10)") (class "Default")
      (node (ref "IC3") (pin "17") (pinfunction "L10_17") (pintype "output"))
      (node (ref "R22") (pin "2") (pinfunction "2_2") (pintype "passive"))
    )
    (net (code "83") (name "Net-(IC3-L11)") (class "Default")
      (node (ref "IC3") (pin "18") (pinfunction "L11_18") (pintype "output"))
      (node (ref "R21") (pin "2") (pinfunction "2_2") (pintype "passive"))
    )
    (net (code "84") (name "Net-(IC3-L12)") (class "Default")
      (node (ref "IC3") (pin "19") (pinfunction "L12_19") (pintype "output"))
      (node (ref "R4") (pin "2") (pinfunction "2_2") (pintype "passive"))
    )
    (net (code "85") (name "Net-(IC3-L13)") (class "Default")
      (node (ref "IC3") (pin "20") (pinfunction "L13_20") (pintype "output"))
      (node (ref "R3") (pin "2") (pinfunction "2_2") (pintype "passive"))
    )
    (net (code "86") (name "SDI_MOSI") (class "Default")
      (node (ref "SERIAL") (pin "8") (pinfunction "8_8") (pintype "passive"))
    )
    (net (code "87") (name "SDI_SCLK") (class "Default")
      (node (ref "SERIAL") (pin "7") (pinfunction "7_7") (pintype "passive"))
    )
    (net (code "88") (name "SLIDER_IN") (class "Default")
      (node (ref "SERIAL") (pin "5") (pinfunction "5_5") (pintype "passive"))
    )
    (net (code "89") (name "unconnected-(IC1-INTA-Pad20)") (class "Default")
      (node (ref "IC1") (pin "20") (pinfunction "INTA_20") (pintype "output"))
    )
    (net (code "90") (name "unconnected-(IC1-INTB-Pad19)") (class "Default")
      (node (ref "IC1") (pin "19") (pinfunction "INTB_19") (pintype "output"))
    )
    (net (code "91") (name "unconnected-(IC3-L14-Pad21)") (class "Default")
      (node (ref "IC3") (pin "21") (pinfunction "L14_21") (pintype "output"))
    )
    (net (code "92") (name "unconnected-(IC3-L15-Pad22)") (class "Default")
      (node (ref "IC3") (pin "22") (pinfunction "L15_22") (pintype "output"))
    )
  )
)
